# offical_board.net
KiCad netlist of a schematic drawn in EAGLE
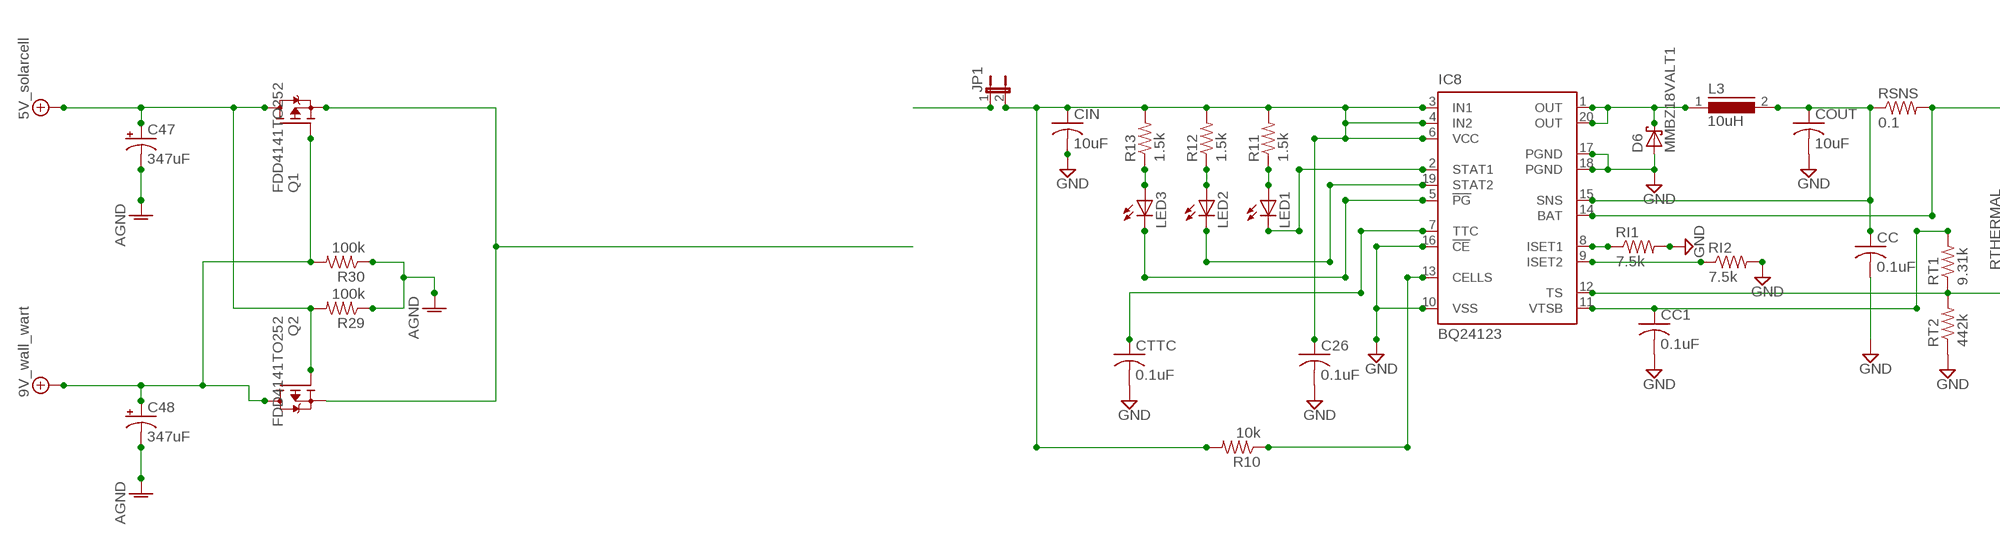
[diagram p0: schematic, sheet 1, part 1 of 2]
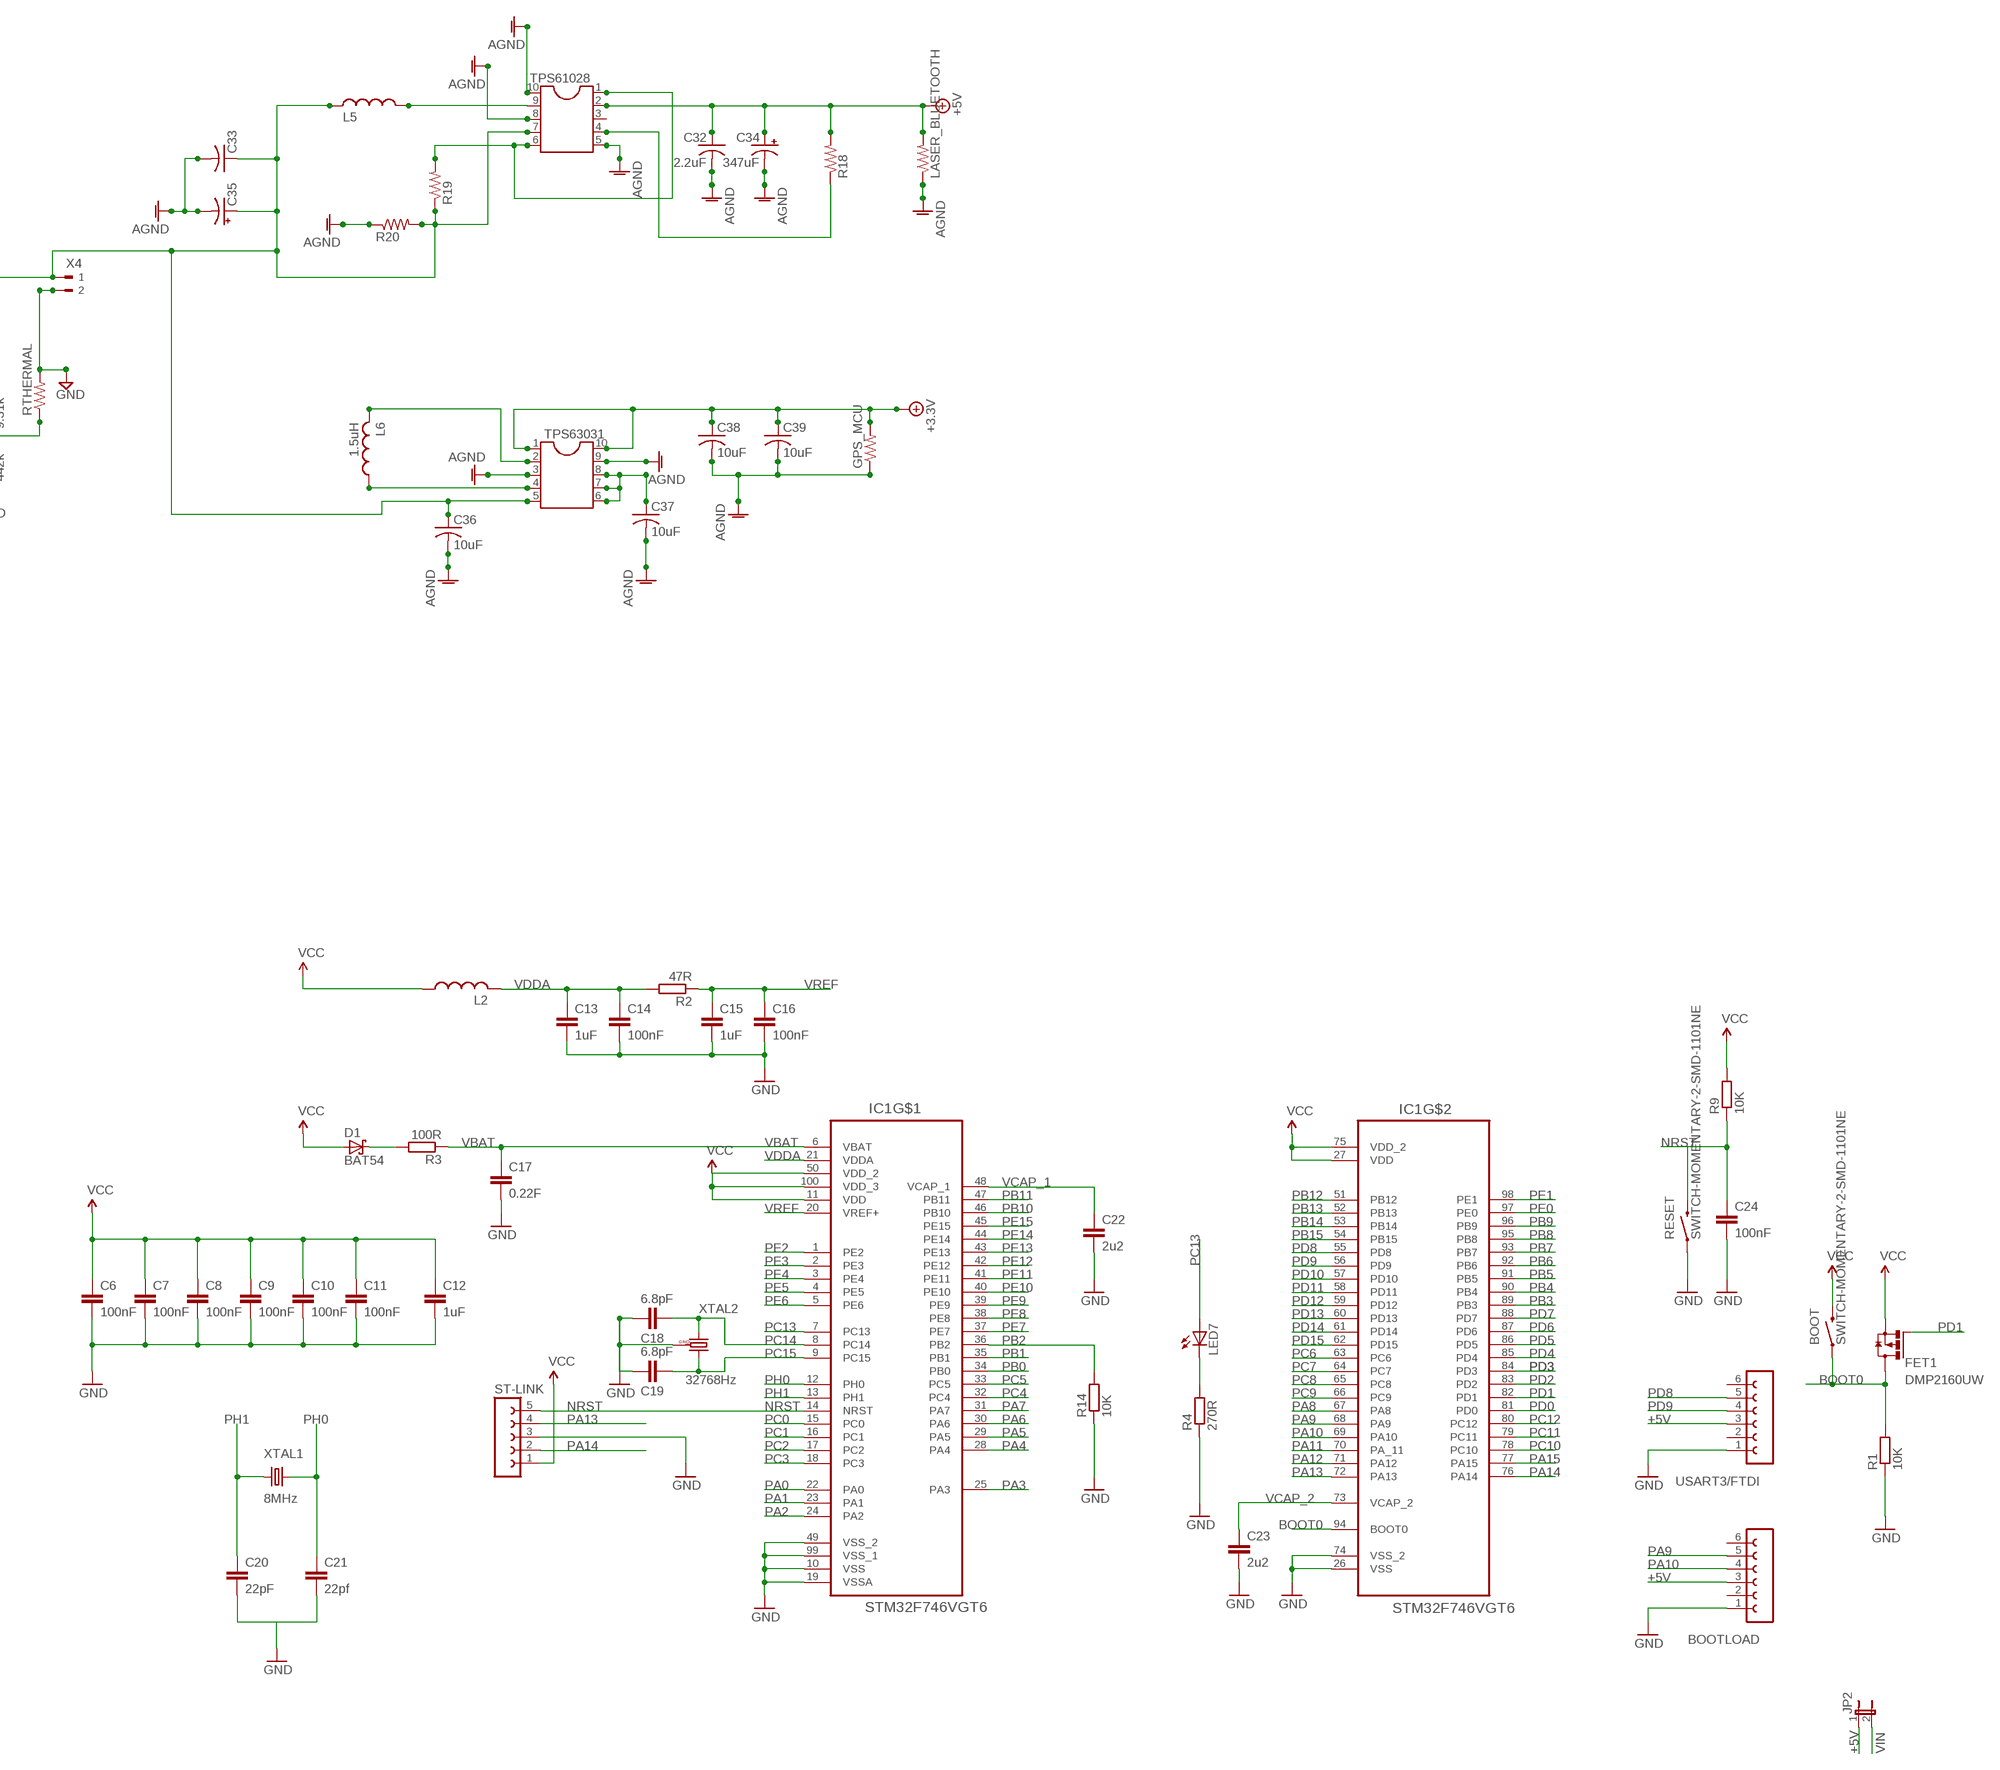
[diagram p1: schematic, sheet 1, part 2 of 2]

(export (version "E")
  (design (tool "Eeschema 10.0.6"))
  (components
    (comp (ref "BOOT")
      (value "SWITCH-MOMENTARY-2-SMD-1101NE")
      (footprint "eagle-import:TACTILE-SWITCH-1101NE")
      (libsource (lib "eagle-import") (part "SWITCH-MOMENTARY-2-SMD-1101NE"))
    )
    (comp (ref "BOOTLOAD")
      (value "FE06-1")
      (footprint "eagle-import:FE06")
      (libsource (lib "eagle-import") (part "FE06-1"))
    )
    (comp (ref "C6")
      (value "100nF")
      (footprint "eagle-import:C0603")
      (libsource (lib "eagle-import") (part "C-EUC0603"))
    )
    (comp (ref "C7")
      (value "100nF")
      (footprint "eagle-import:C0603")
      (libsource (lib "eagle-import") (part "C-EUC0603"))
    )
    (comp (ref "C8")
      (value "100nF")
      (footprint "eagle-import:C0603")
      (libsource (lib "eagle-import") (part "C-EUC0603"))
    )
    (comp (ref "C9")
      (value "100nF")
      (footprint "eagle-import:C0603")
      (libsource (lib "eagle-import") (part "C-EUC0603"))
    )
    (comp (ref "C10")
      (value "100nF")
      (footprint "eagle-import:C0603")
      (libsource (lib "eagle-import") (part "C-EUC0603"))
    )
    (comp (ref "C11")
      (value "100nF")
      (footprint "eagle-import:C0603")
      (libsource (lib "eagle-import") (part "C-EUC0603"))
    )
    (comp (ref "C12")
      (value "1uF")
      (footprint "eagle-import:C0603")
      (libsource (lib "eagle-import") (part "C-EUC0603"))
    )
    (comp (ref "C13")
      (value "1uF")
      (footprint "eagle-import:C0603")
      (libsource (lib "eagle-import") (part "C-EUC0603"))
    )
    (comp (ref "C14")
      (value "100nF")
      (footprint "eagle-import:C0603")
      (libsource (lib "eagle-import") (part "C-EUC0603"))
    )
    (comp (ref "C15")
      (value "1uF")
      (footprint "eagle-import:C0603")
      (libsource (lib "eagle-import") (part "C-EUC0603"))
    )
    (comp (ref "C16")
      (value "100nF")
      (footprint "eagle-import:C0603")
      (libsource (lib "eagle-import") (part "C-EUC0603"))
    )
    (comp (ref "C17")
      (value "0.22F")
      (footprint "eagle-import:C5B5")
      (libsource (lib "eagle-import") (part "C5/5"))
    )
    (comp (ref "C18")
      (value "6.8pF")
      (footprint "eagle-import:C0603")
      (libsource (lib "eagle-import") (part "C-EUC0603"))
    )
    (comp (ref "C19")
      (value "6.8pF")
      (footprint "eagle-import:C0603")
      (libsource (lib "eagle-import") (part "C-EUC0603"))
    )
    (comp (ref "C20")
      (value "22pF")
      (footprint "eagle-import:C0603")
      (libsource (lib "eagle-import") (part "C-EUC0603"))
    )
    (comp (ref "C21")
      (value "22pf")
      (footprint "eagle-import:C0603")
      (libsource (lib "eagle-import") (part "C-EUC0603"))
    )
    (comp (ref "C22")
      (value "2u2")
      (footprint "eagle-import:C0603")
      (libsource (lib "eagle-import") (part "C-EUC0603"))
    )
    (comp (ref "C23")
      (value "2u2")
      (footprint "eagle-import:C0603")
      (libsource (lib "eagle-import") (part "C-EUC0603"))
    )
    (comp (ref "C24")
      (value "100nF")
      (footprint "eagle-import:C0603")
      (libsource (lib "eagle-import") (part "C-EUC0603"))
    )
    (comp (ref "C26")
      (value "0.1uF")
      (footprint "eagle-import:C0805")
      (libsource (lib "eagle-import") (part "C-USC0805"))
    )
    (comp (ref "C32")
      (value "2.2uF")
      (footprint "eagle-import:C0603")
      (libsource (lib "eagle-import") (part "C-USC0603"))
    )
    (comp (ref "C33")
      (value "C-USC0603")
      (footprint "eagle-import:C0603")
      (libsource (lib "eagle-import") (part "C-USC0603"))
    )
    (comp (ref "C34")
      (value "347uF")
      (footprint "eagle-import:150CLZ-0810")
      (libsource (lib "eagle-import") (part "CPOL-US150CLZ-0810"))
    )
    (comp (ref "C35")
      (value "CPOL-US150CLZ-0810")
      (footprint "eagle-import:150CLZ-0810")
      (libsource (lib "eagle-import") (part "CPOL-US150CLZ-0810"))
    )
    (comp (ref "C36")
      (value "10uF")
      (footprint "eagle-import:C0603")
      (libsource (lib "eagle-import") (part "C-USC0603"))
    )
    (comp (ref "C37")
      (value "10uF")
      (footprint "eagle-import:C0603")
      (libsource (lib "eagle-import") (part "C-USC0603"))
    )
    (comp (ref "C38")
      (value "10uF")
      (footprint "eagle-import:C0603")
      (libsource (lib "eagle-import") (part "C-USC0603"))
    )
    (comp (ref "C39")
      (value "10uF")
      (footprint "eagle-import:C0603")
      (libsource (lib "eagle-import") (part "C-USC0603"))
    )
    (comp (ref "C47")
      (value "347uF")
      (footprint "eagle-import:150CLZ-0810")
      (libsource (lib "eagle-import") (part "CPOL-US150CLZ-0810"))
    )
    (comp (ref "C48")
      (value "347uF")
      (footprint "eagle-import:150CLZ-0810")
      (libsource (lib "eagle-import") (part "CPOL-US150CLZ-0810"))
    )
    (comp (ref "CC")
      (value "0.1uF")
      (footprint "eagle-import:C0805")
      (libsource (lib "eagle-import") (part "C-USC0805"))
    )
    (comp (ref "CC1")
      (value "0.1uF")
      (footprint "eagle-import:C0805")
      (libsource (lib "eagle-import") (part "C-USC0805"))
    )
    (comp (ref "CIN")
      (value "10uF")
      (footprint "eagle-import:C0805")
      (libsource (lib "eagle-import") (part "C-USC0805"))
    )
    (comp (ref "COUT")
      (value "10uF")
      (footprint "eagle-import:C0805")
      (libsource (lib "eagle-import") (part "C-USC0805"))
    )
    (comp (ref "CTTC")
      (value "0.1uF")
      (footprint "eagle-import:C0805")
      (libsource (lib "eagle-import") (part "C-USC0805"))
    )
    (comp (ref "D1")
      (value "BAT54")
      (footprint "eagle-import:SOT23")
      (libsource (lib "eagle-import") (part "BAT54"))
    )
    (comp (ref "D6")
      (value "MMBZ18VALT1")
      (footprint "eagle-import:C4111-15")
      (libsource (lib "eagle-import") (part "1N5908"))
    )
    (comp (ref "FET1")
      (value "DMP2160UW")
      (footprint "eagle-import:SUPER-SOT3")
      (libsource (lib "eagle-import") (part "FDN360P"))
    )
    (comp (ref "GPS_MCU")
      (value "R-US_R0603")
      (footprint "eagle-import:R0603")
      (libsource (lib "eagle-import") (part "R-US_R0603"))
    )
    (comp (ref "IC1")
      (value "STM32F746VGT6")
      (footprint "eagle-import:QFP50P1600X1600X160-100N")
      (libsource (lib "eagle-import") (part "STM32F746VGT6"))
    )
    (comp (ref "IC8")
      (value "BQ24123")
      (footprint "eagle-import:QFN20_3,5X4,5")
      (fields (field (name "MPN") "BQ24123RHLT"))
      (libsource (lib "eagle-import") (part "BQ24123"))
    )
    (comp (ref "JP1")
      (value "JP1E")
      (footprint "eagle-import:JP1")
      (libsource (lib "eagle-import") (part "JP1E"))
    )
    (comp (ref "JP2")
      (value "JP1E")
      (footprint "eagle-import:JP1")
      (libsource (lib "eagle-import") (part "JP1E"))
    )
    (comp (ref "L2")
      (value "RCL_L-USL0603")
      (footprint "eagle-import:RCL_L0603")
      (libsource (lib "eagle-import") (part "RCL_L-USL0603"))
    )
    (comp (ref "L3")
      (value "10uH")
      (footprint "eagle-import:DR73")
      (libsource (lib "eagle-import") (part "DR73"))
    )
    (comp (ref "L5")
      (value "L-USL2825P")
      (footprint "eagle-import:L2825P")
      (libsource (lib "eagle-import") (part "L-USL2825P"))
    )
    (comp (ref "L6")
      (value "1.5uH")
      (footprint "eagle-import:L2825P")
      (libsource (lib "eagle-import") (part "L-USL2825P"))
    )
    (comp (ref "LASER_BLUETOOTH")
      (value "R-US_R0603")
      (footprint "eagle-import:R0603")
      (libsource (lib "eagle-import") (part "R-US_R0603"))
    )
    (comp (ref "LED1")
      (value "SFH482")
      (footprint "eagle-import:SFH482")
      (libsource (lib "eagle-import") (part "SFH482"))
    )
    (comp (ref "LED2")
      (value "SFH482")
      (footprint "eagle-import:SFH482")
      (libsource (lib "eagle-import") (part "SFH482"))
    )
    (comp (ref "LED3")
      (value "SFH482")
      (footprint "eagle-import:SFH482")
      (libsource (lib "eagle-import") (part "SFH482"))
    )
    (comp (ref "LED7")
      (value "LEDCHIP-LED0603")
      (footprint "eagle-import:CHIP-LED0603")
      (libsource (lib "eagle-import") (part "LEDCHIP-LED0603"))
    )
    (comp (ref "Q1")
      (value "FDD4141TO252")
      (footprint "eagle-import:TO252")
      (libsource (lib "eagle-import") (part "FDD4141TO252"))
    )
    (comp (ref "Q2")
      (value "FDD4141TO252")
      (footprint "eagle-import:TO252")
      (libsource (lib "eagle-import") (part "FDD4141TO252"))
    )
    (comp (ref "R1")
      (value "10K")
      (footprint "eagle-import:R0603")
      (libsource (lib "eagle-import") (part "R-EU_R0603"))
    )
    (comp (ref "R2")
      (value "47R")
      (footprint "eagle-import:R0603")
      (libsource (lib "eagle-import") (part "R-EU_R0603"))
    )
    (comp (ref "R3")
      (value "100R")
      (footprint "eagle-import:R0603")
      (libsource (lib "eagle-import") (part "resistor_R-EU_R0603"))
    )
    (comp (ref "R4")
      (value "270R")
      (footprint "eagle-import:R0603")
      (libsource (lib "eagle-import") (part "resistor_R-EU_R0603"))
    )
    (comp (ref "R9")
      (value "10K")
      (footprint "eagle-import:R0603")
      (libsource (lib "eagle-import") (part "R-EU_R0603"))
    )
    (comp (ref "R10")
      (value "10k")
      (footprint "eagle-import:R0805")
      (libsource (lib "eagle-import") (part "R-US_R0805"))
    )
    (comp (ref "R11")
      (value "1.5k")
      (footprint "eagle-import:R0805")
      (libsource (lib "eagle-import") (part "R-US_R0805"))
    )
    (comp (ref "R12")
      (value "1.5k")
      (footprint "eagle-import:R0805")
      (libsource (lib "eagle-import") (part "R-US_R0805"))
    )
    (comp (ref "R13")
      (value "1.5k")
      (footprint "eagle-import:R0805")
      (libsource (lib "eagle-import") (part "R-US_R0805"))
    )
    (comp (ref "R14")
      (value "10K")
      (footprint "eagle-import:R0603")
      (libsource (lib "eagle-import") (part "R-EU_R0603"))
    )
    (comp (ref "R18")
      (value "R-US_R0603")
      (footprint "eagle-import:R0603")
      (libsource (lib "eagle-import") (part "R-US_R0603"))
    )
    (comp (ref "R19")
      (value "R-US_R0603")
      (footprint "eagle-import:R0603")
      (libsource (lib "eagle-import") (part "R-US_R0603"))
    )
    (comp (ref "R20")
      (value "R-US_R0603")
      (footprint "eagle-import:R0603")
      (libsource (lib "eagle-import") (part "R-US_R0603"))
    )
    (comp (ref "R29")
      (value "100k")
      (footprint "eagle-import:R0603")
      (libsource (lib "eagle-import") (part "R-US_R0603"))
    )
    (comp (ref "R30")
      (value "100k")
      (footprint "eagle-import:R0603")
      (libsource (lib "eagle-import") (part "R-US_R0603"))
    )
    (comp (ref "RESET")
      (value "SWITCH-MOMENTARY-2-SMD-1101NE")
      (footprint "eagle-import:TACTILE-SWITCH-1101NE")
      (libsource (lib "eagle-import") (part "SWITCH-MOMENTARY-2-SMD-1101NE"))
    )
    (comp (ref "RI1")
      (value "7.5k")
      (footprint "eagle-import:R0805")
      (libsource (lib "eagle-import") (part "R-US_R0805"))
    )
    (comp (ref "RI2")
      (value "7.5k")
      (footprint "eagle-import:R0805")
      (libsource (lib "eagle-import") (part "R-US_R0805"))
    )
    (comp (ref "RSNS")
      (value "0.1")
      (footprint "eagle-import:R1206")
      (libsource (lib "eagle-import") (part "R-US_R1206"))
    )
    (comp (ref "RT1")
      (value "9.31k")
      (footprint "eagle-import:R0805")
      (libsource (lib "eagle-import") (part "R-US_R0805"))
    )
    (comp (ref "RT2")
      (value "442k")
      (footprint "eagle-import:R0805")
      (libsource (lib "eagle-import") (part "R-US_R0805"))
    )
    (comp (ref "RTHERMAL")
      (value "R-US_R0805")
      (footprint "eagle-import:R0805")
      (libsource (lib "eagle-import") (part "R-US_R0805"))
    )
    (comp (ref "ST-LINK")
      (value "FE05-1")
      (footprint "eagle-import:FE05-1")
      (libsource (lib "eagle-import") (part "FE05-1"))
    )
    (comp (ref "TPS61028")
      (value "DIL10")
      (footprint "eagle-import:DIL10")
      (libsource (lib "eagle-import") (part "DIL10"))
    )
    (comp (ref "TPS63031")
      (value "DIL10")
      (footprint "eagle-import:DIL10")
      (libsource (lib "eagle-import") (part "DIL10"))
    )
    (comp (ref "USART3/FTDI")
      (value "FE06-1")
      (footprint "eagle-import:FE06")
      (libsource (lib "eagle-import") (part "FE06-1"))
    )
    (comp (ref "X4")
      (value "90-2")
      (footprint "eagle-import:90-2")
      (libsource (lib "eagle-import") (part "90-2"))
    )
    (comp (ref "XTAL1")
      (value "8MHz")
      (footprint "eagle-import:HC49U-V")
      (libsource (lib "eagle-import") (part "CRYSTALHC49U-V"))
    )
    (comp (ref "XTAL2")
      (value "32768Hz")
      (footprint "eagle-import:CRYSTAL_TC26H_3_REPAIR_SMD_SMALL_PITCH")
      (libsource (lib "eagle-import") (part "CRYSTAL_Q_GNDS"))
    )
  )
  (nets
    (net (code "1") (name "+3.3V") (class "Default")
      (node (ref "BOOTLOAD") (pin "3") (pinfunction "3_3") (pintype "passive"))
      (node (ref "C32") (pin "1") (pinfunction "1_1") (pintype "passive"))
      (node (ref "C34") (pin "+") (pinfunction "+_+") (pintype "passive"))
      (node (ref "C38") (pin "1") (pinfunction "1_1") (pintype "passive"))
      (node (ref "C39") (pin "1") (pinfunction "1_1") (pintype "passive"))
      (node (ref "C47") (pin "+") (pinfunction "+_+") (pintype "passive"))
      (node (ref "C48") (pin "+") (pinfunction "+_+") (pintype "passive"))
      (node (ref "GPS_MCU") (pin "2") (pinfunction "2_2") (pintype "passive"))
      (node (ref "JP2") (pin "1") (pinfunction "1_1") (pintype "passive"))
      (node (ref "LASER_BLUETOOTH") (pin "2") (pinfunction "2_2") (pintype "passive"))
      (node (ref "Q1") (pin "1") (pinfunction "G_1") (pintype "passive"))
      (node (ref "Q1") (pin "3") (pinfunction "D_3") (pintype "passive"))
      (node (ref "Q2") (pin "1") (pinfunction "G_1") (pintype "passive"))
      (node (ref "Q2") (pin "3") (pinfunction "D_3") (pintype "passive"))
      (node (ref "R18") (pin "2") (pinfunction "2_2") (pintype "passive"))
      (node (ref "R29") (pin "2") (pinfunction "2_2") (pintype "passive"))
      (node (ref "R30") (pin "2") (pinfunction "2_2") (pintype "passive"))
      (node (ref "TPS61028") (pin "2") (pinfunction "2_2") (pintype "passive"))
      (node (ref "TPS63031") (pin "1") (pinfunction "1_1") (pintype "passive"))
      (node (ref "TPS63031") (pin "10") (pinfunction "10_10") (pintype "passive"))
      (node (ref "USART3/FTDI") (pin "3") (pinfunction "3_3") (pintype "passive"))
    )
    (net (code "2") (name "/BOOT0") (class "Default")
      (node (ref "BOOT") (pin "P$1") (pinfunction "1_P$1") (pintype "passive"))
      (node (ref "FET1") (pin "3") (pinfunction "D_3") (pintype "passive"))
      (node (ref "IC1") (pin "94") (pinfunction "BOOT0_94") (pintype "input"))
      (node (ref "R1") (pin "2") (pinfunction "2_2") (pintype "passive"))
    )
    (net (code "3") (name "/NRST") (class "Default")
      (node (ref "C24") (pin "1") (pinfunction "1_1") (pintype "passive"))
      (node (ref "IC1") (pin "14") (pinfunction "NRST_14") (pintype "bidirectional"))
      (node (ref "R9") (pin "1") (pinfunction "1_1") (pintype "passive"))
      (node (ref "RESET") (pin "P$2") (pinfunction "2_P$2") (pintype "passive"))
      (node (ref "ST-LINK") (pin "5") (pinfunction "5_5") (pintype "passive"))
    )
    (net (code "4") (name "/PA0") (class "Default")
      (node (ref "IC1") (pin "22") (pinfunction "PA0_22") (pintype "bidirectional"))
    )
    (net (code "5") (name "/PA1") (class "Default")
      (node (ref "IC1") (pin "23") (pinfunction "PA1_23") (pintype "bidirectional"))
    )
    (net (code "6") (name "/PA2") (class "Default")
      (node (ref "IC1") (pin "24") (pinfunction "PA2_24") (pintype "bidirectional"))
    )
    (net (code "7") (name "/PA3") (class "Default")
      (node (ref "IC1") (pin "25") (pinfunction "PA3_25") (pintype "bidirectional"))
    )
    (net (code "8") (name "/PA4") (class "Default")
      (node (ref "IC1") (pin "28") (pinfunction "PA4_28") (pintype "bidirectional"))
    )
    (net (code "9") (name "/PA5") (class "Default")
      (node (ref "IC1") (pin "29") (pinfunction "PA5_29") (pintype "bidirectional"))
    )
    (net (code "10") (name "/PA6") (class "Default")
      (node (ref "IC1") (pin "30") (pinfunction "PA6_30") (pintype "bidirectional"))
    )
    (net (code "11") (name "/PA7") (class "Default")
      (node (ref "IC1") (pin "31") (pinfunction "PA7_31") (pintype "bidirectional"))
    )
    (net (code "12") (name "/PA8") (class "Default")
      (node (ref "IC1") (pin "67") (pinfunction "PA8_67") (pintype "bidirectional"))
    )
    (net (code "13") (name "/PA9") (class "Default")
      (node (ref "BOOTLOAD") (pin "5") (pinfunction "5_5") (pintype "passive"))
      (node (ref "IC1") (pin "68") (pinfunction "PA9_68") (pintype "bidirectional"))
    )
    (net (code "14") (name "/PA10") (class "Default")
      (node (ref "BOOTLOAD") (pin "4") (pinfunction "4_4") (pintype "passive"))
      (node (ref "IC1") (pin "69") (pinfunction "PA10_69") (pintype "bidirectional"))
    )
    (net (code "15") (name "/PA11") (class "Default")
      (node (ref "IC1") (pin "70") (pinfunction "PA_11_70") (pintype "bidirectional"))
    )
    (net (code "16") (name "/PA12") (class "Default")
      (node (ref "IC1") (pin "71") (pinfunction "PA12_71") (pintype "bidirectional"))
    )
    (net (code "17") (name "/PA13") (class "Default")
      (node (ref "IC1") (pin "72") (pinfunction "PA13_72") (pintype "bidirectional"))
      (node (ref "ST-LINK") (pin "4") (pinfunction "4_4") (pintype "passive"))
    )
    (net (code "18") (name "/PA14") (class "Default")
      (node (ref "IC1") (pin "76") (pinfunction "PA14_76") (pintype "bidirectional"))
      (node (ref "ST-LINK") (pin "2") (pinfunction "2_2") (pintype "passive"))
    )
    (net (code "19") (name "/PA15") (class "Default")
      (node (ref "IC1") (pin "77") (pinfunction "PA15_77") (pintype "bidirectional"))
    )
    (net (code "20") (name "/PB0") (class "Default")
      (node (ref "IC1") (pin "34") (pinfunction "PB0_34") (pintype "bidirectional"))
    )
    (net (code "21") (name "/PB1") (class "Default")
      (node (ref "IC1") (pin "35") (pinfunction "PB1_35") (pintype "bidirectional"))
    )
    (net (code "22") (name "/PB2") (class "Default")
      (node (ref "IC1") (pin "36") (pinfunction "PB2_36") (pintype "bidirectional"))
      (node (ref "R14") (pin "2") (pinfunction "2_2") (pintype "passive"))
    )
    (net (code "23") (name "/PB3") (class "Default")
      (node (ref "IC1") (pin "89") (pinfunction "PB3_89") (pintype "bidirectional"))
    )
    (net (code "24") (name "/PB4") (class "Default")
      (node (ref "IC1") (pin "90") (pinfunction "PB4_90") (pintype "bidirectional"))
    )
    (net (code "25") (name "/PB5") (class "Default")
      (node (ref "IC1") (pin "91") (pinfunction "PB5_91") (pintype "bidirectional"))
    )
    (net (code "26") (name "/PB6") (class "Default")
      (node (ref "IC1") (pin "92") (pinfunction "PB6_92") (pintype "bidirectional"))
    )
    (net (code "27") (name "/PB7") (class "Default")
      (node (ref "IC1") (pin "93") (pinfunction "PB7_93") (pintype "bidirectional"))
    )
    (net (code "28") (name "/PB8") (class "Default")
      (node (ref "IC1") (pin "95") (pinfunction "PB8_95") (pintype "bidirectional"))
    )
    (net (code "29") (name "/PB9") (class "Default")
      (node (ref "IC1") (pin "96") (pinfunction "PB9_96") (pintype "bidirectional"))
    )
    (net (code "30") (name "/PB10") (class "Default")
      (node (ref "IC1") (pin "46") (pinfunction "PB10_46") (pintype "bidirectional"))
    )
    (net (code "31") (name "/PB11") (class "Default")
      (node (ref "IC1") (pin "47") (pinfunction "PB11_47") (pintype "bidirectional"))
    )
    (net (code "32") (name "/PB12") (class "Default")
      (node (ref "IC1") (pin "51") (pinfunction "PB12_51") (pintype "bidirectional"))
    )
    (net (code "33") (name "/PB13") (class "Default")
      (node (ref "IC1") (pin "52") (pinfunction "PB13_52") (pintype "bidirectional"))
    )
    (net (code "34") (name "/PB14") (class "Default")
      (node (ref "IC1") (pin "53") (pinfunction "PB14_53") (pintype "bidirectional"))
    )
    (net (code "35") (name "/PB15") (class "Default")
      (node (ref "IC1") (pin "54") (pinfunction "PB15_54") (pintype "bidirectional"))
    )
    (net (code "36") (name "/PC0") (class "Default")
      (node (ref "IC1") (pin "15") (pinfunction "PC0_15") (pintype "bidirectional"))
    )
    (net (code "37") (name "/PC1") (class "Default")
      (node (ref "IC1") (pin "16") (pinfunction "PC1_16") (pintype "bidirectional"))
    )
    (net (code "38") (name "/PC2") (class "Default")
      (node (ref "IC1") (pin "17") (pinfunction "PC2_17") (pintype "bidirectional"))
    )
    (net (code "39") (name "/PC3") (class "Default")
      (node (ref "IC1") (pin "18") (pinfunction "PC3_18") (pintype "bidirectional"))
    )
    (net (code "40") (name "/PC4") (class "Default")
      (node (ref "IC1") (pin "32") (pinfunction "PC4_32") (pintype "bidirectional"))
    )
    (net (code "41") (name "/PC5") (class "Default")
      (node (ref "IC1") (pin "33") (pinfunction "PC5_33") (pintype "bidirectional"))
    )
    (net (code "42") (name "/PC6") (class "Default")
      (node (ref "IC1") (pin "63") (pinfunction "PC6_63") (pintype "bidirectional"))
    )
    (net (code "43") (name "/PC7") (class "Default")
      (node (ref "IC1") (pin "64") (pinfunction "PC7_64") (pintype "bidirectional"))
    )
    (net (code "44") (name "/PC8") (class "Default")
      (node (ref "IC1") (pin "65") (pinfunction "PC8_65") (pintype "bidirectional"))
    )
    (net (code "45") (name "/PC9") (class "Default")
      (node (ref "IC1") (pin "66") (pinfunction "PC9_66") (pintype "bidirectional"))
    )
    (net (code "46") (name "/PC10") (class "Default")
      (node (ref "IC1") (pin "78") (pinfunction "PC10_78") (pintype "bidirectional"))
    )
    (net (code "47") (name "/PC11") (class "Default")
      (node (ref "IC1") (pin "79") (pinfunction "PC11_79") (pintype "bidirectional"))
    )
    (net (code "48") (name "/PC12") (class "Default")
      (node (ref "IC1") (pin "80") (pinfunction "PC12_80") (pintype "bidirectional"))
    )
    (net (code "49") (name "/PC13") (class "Default")
      (node (ref "IC1") (pin "7") (pinfunction "PC13_7") (pintype "bidirectional"))
      (node (ref "LED7") (pin "A") (pinfunction "A_A") (pintype "passive"))
    )
    (net (code "50") (name "/PC14") (class "Default")
      (node (ref "C18") (pin "1") (pinfunction "1_1") (pintype "passive"))
      (node (ref "IC1") (pin "8") (pinfunction "PC14_8") (pintype "bidirectional"))
      (node (ref "XTAL2") (pin "1") (pinfunction "1_1") (pintype "passive"))
    )
    (net (code "51") (name "/PC15") (class "Default")
      (node (ref "C19") (pin "1") (pinfunction "1_1") (pintype "passive"))
      (node (ref "IC1") (pin "9") (pinfunction "PC15_9") (pintype "bidirectional"))
      (node (ref "XTAL2") (pin "2") (pinfunction "2_2") (pintype "passive"))
    )
    (net (code "52") (name "/PD0") (class "Default")
      (node (ref "IC1") (pin "81") (pinfunction "PD0_81") (pintype "bidirectional"))
    )
    (net (code "53") (name "/PD1") (class "Default")
      (node (ref "FET1") (pin "1") (pinfunction "G_1") (pintype "passive"))
      (node (ref "IC1") (pin "82") (pinfunction "PD1_82") (pintype "bidirectional"))
    )
    (net (code "54") (name "/PD2") (class "Default")
      (node (ref "IC1") (pin "83") (pinfunction "PD2_83") (pintype "bidirectional"))
    )
    (net (code "55") (name "/PD3") (class "Default")
      (node (ref "IC1") (pin "84") (pinfunction "PD3_84") (pintype "bidirectional"))
    )
    (net (code "56") (name "/PD4") (class "Default")
      (node (ref "IC1") (pin "85") (pinfunction "PD4_85") (pintype "bidirectional"))
    )
    (net (code "57") (name "/PD5") (class "Default")
      (node (ref "IC1") (pin "86") (pinfunction "PD5_86") (pintype "bidirectional"))
    )
    (net (code "58") (name "/PD6") (class "Default")
      (node (ref "IC1") (pin "87") (pinfunction "PD6_87") (pintype "bidirectional"))
    )
    (net (code "59") (name "/PD7") (class "Default")
      (node (ref "IC1") (pin "88") (pinfunction "PD7_88") (pintype "bidirectional"))
    )
    (net (code "60") (name "/PD8") (class "Default")
      (node (ref "IC1") (pin "55") (pinfunction "PD8_55") (pintype "bidirectional"))
      (node (ref "USART3/FTDI") (pin "5") (pinfunction "5_5") (pintype "passive"))
    )
    (net (code "61") (name "/PD9") (class "Default")
      (node (ref "IC1") (pin "56") (pinfunction "PD9_56") (pintype "bidirectional"))
      (node (ref "USART3/FTDI") (pin "4") (pinfunction "4_4") (pintype "passive"))
    )
    (net (code "62") (name "/PD10") (class "Default")
      (node (ref "IC1") (pin "57") (pinfunction "PD10_57") (pintype "bidirectional"))
    )
    (net (code "63") (name "/PD11") (class "Default")
      (node (ref "IC1") (pin "58") (pinfunction "PD11_58") (pintype "bidirectional"))
    )
    (net (code "64") (name "/PD12") (class "Default")
      (node (ref "IC1") (pin "59") (pinfunction "PD12_59") (pintype "bidirectional"))
    )
    (net (code "65") (name "/PD13") (class "Default")
      (node (ref "IC1") (pin "60") (pinfunction "PD13_60") (pintype "bidirectional"))
    )
    (net (code "66") (name "/PD14") (class "Default")
      (node (ref "IC1") (pin "61") (pinfunction "PD14_61") (pintype "bidirectional"))
    )
    (net (code "67") (name "/PD15") (class "Default")
      (node (ref "IC1") (pin "62") (pinfunction "PD15_62") (pintype "bidirectional"))
    )
    (net (code "68") (name "/PE0") (class "Default")
      (node (ref "IC1") (pin "97") (pinfunction "PE0_97") (pintype "bidirectional"))
    )
    (net (code "69") (name "/PE1") (class "Default")
      (node (ref "IC1") (pin "98") (pinfunction "PE1_98") (pintype "bidirectional"))
    )
    (net (code "70") (name "/PE2") (class "Default")
      (node (ref "IC1") (pin "1") (pinfunction "PE2_1") (pintype "bidirectional"))
    )
    (net (code "71") (name "/PE3") (class "Default")
      (node (ref "IC1") (pin "2") (pinfunction "PE3_2") (pintype "bidirectional"))
    )
    (net (code "72") (name "/PE4") (class "Default")
      (node (ref "IC1") (pin "3") (pinfunction "PE4_3") (pintype "bidirectional"))
    )
    (net (code "73") (name "/PE5") (class "Default")
      (node (ref "IC1") (pin "4") (pinfunction "PE5_4") (pintype "bidirectional"))
    )
    (net (code "74") (name "/PE6") (class "Default")
      (node (ref "IC1") (pin "5") (pinfunction "PE6_5") (pintype "bidirectional"))
    )
    (net (code "75") (name "/PE7") (class "Default")
      (node (ref "IC1") (pin "37") (pinfunction "PE7_37") (pintype "bidirectional"))
    )
    (net (code "76") (name "/PE8") (class "Default")
      (node (ref "IC1") (pin "38") (pinfunction "PE8_38") (pintype "bidirectional"))
    )
    (net (code "77") (name "/PE9") (class "Default")
      (node (ref "IC1") (pin "39") (pinfunction "PE9_39") (pintype "bidirectional"))
    )
    (net (code "78") (name "/PE10") (class "Default")
      (node (ref "IC1") (pin "40") (pinfunction "PE10_40") (pintype "bidirectional"))
    )
    (net (code "79") (name "/PE11") (class "Default")
      (node (ref "IC1") (pin "41") (pinfunction "PE11_41") (pintype "bidirectional"))
    )
    (net (code "80") (name "/PE12") (class "Default")
      (node (ref "IC1") (pin "42") (pinfunction "PE12_42") (pintype "bidirectional"))
    )
    (net (code "81") (name "/PE13") (class "Default")
      (node (ref "IC1") (pin "43") (pinfunction "PE13_43") (pintype "bidirectional"))
    )
    (net (code "82") (name "/PE14") (class "Default")
      (node (ref "IC1") (pin "44") (pinfunction "PE14_44") (pintype "bidirectional"))
    )
    (net (code "83") (name "/PE15") (class "Default")
      (node (ref "IC1") (pin "45") (pinfunction "PE15_45") (pintype "bidirectional"))
    )
    (net (code "84") (name "/PH0") (class "Default")
      (node (ref "C21") (pin "1") (pinfunction "1_1") (pintype "passive"))
      (node (ref "IC1") (pin "12") (pinfunction "PH0_12") (pintype "bidirectional"))
      (node (ref "XTAL1") (pin "2") (pinfunction "2_2") (pintype "passive"))
    )
    (net (code "85") (name "/PH1") (class "Default")
      (node (ref "C20") (pin "1") (pinfunction "1_1") (pintype "passive"))
      (node (ref "IC1") (pin "13") (pinfunction "PH1_13") (pintype "bidirectional"))
      (node (ref "XTAL1") (pin "1") (pinfunction "1_1") (pintype "passive"))
    )
    (net (code "86") (name "/VBAT") (class "Default")
      (node (ref "C17") (pin "1") (pinfunction "1_1") (pintype "passive"))
      (node (ref "IC1") (pin "6") (pinfunction "VBAT_6") (pintype "power_in"))
      (node (ref "R3") (pin "1") (pinfunction "1_1") (pintype "passive"))
    )
    (net (code "87") (name "/VCAP_1") (class "Default")
      (node (ref "C22") (pin "1") (pinfunction "1_1") (pintype "passive"))
      (node (ref "IC1") (pin "48") (pinfunction "VCAP_1_48") (pintype "power_in"))
    )
    (net (code "88") (name "/VCAP_2") (class "Default")
      (node (ref "C23") (pin "1") (pinfunction "1_1") (pintype "passive"))
      (node (ref "IC1") (pin "73") (pinfunction "VCAP_2_73") (pintype "power_in"))
    )
    (net (code "89") (name "/VDDA") (class "Default")
      (node (ref "C13") (pin "1") (pinfunction "1_1") (pintype "passive"))
      (node (ref "C14") (pin "1") (pinfunction "1_1") (pintype "passive"))
      (node (ref "IC1") (pin "21") (pinfunction "VDDA_21") (pintype "power_in"))
      (node (ref "L2") (pin "2") (pinfunction "2_2") (pintype "passive"))
      (node (ref "R2") (pin "2") (pinfunction "2_2") (pintype "passive"))
    )
    (net (code "90") (name "/VIN") (class "Default")
      (node (ref "JP2") (pin "2") (pinfunction "2_2") (pintype "passive"))
    )
    (net (code "91") (name "/VREF") (class "Default")
      (node (ref "C15") (pin "1") (pinfunction "1_1") (pintype "passive"))
      (node (ref "C16") (pin "1") (pinfunction "1_1") (pintype "passive"))
      (node (ref "IC1") (pin "20") (pinfunction "VREF+_20") (pintype "power_in"))
      (node (ref "R2") (pin "1") (pinfunction "1_1") (pintype "passive"))
    )
    (net (code "92") (name "AGND") (class "Default")
      (node (ref "C32") (pin "2") (pinfunction "2_2") (pintype "passive"))
      (node (ref "C33") (pin "2") (pinfunction "2_2") (pintype "passive"))
      (node (ref "C34") (pin "-") (pinfunction "-_-") (pintype "passive"))
      (node (ref "C35") (pin "-") (pinfunction "-_-") (pintype "passive"))
      (node (ref "C36") (pin "2") (pinfunction "2_2") (pintype "passive"))
      (node (ref "C37") (pin "2") (pinfunction "2_2") (pintype "passive"))
      (node (ref "C38") (pin "2") (pinfunction "2_2") (pintype "passive"))
      (node (ref "C39") (pin "2") (pinfunction "2_2") (pintype "passive"))
      (node (ref "C47") (pin "-") (pinfunction "-_-") (pintype "passive"))
      (node (ref "C48") (pin "-") (pinfunction "-_-") (pintype "passive"))
      (node (ref "GPS_MCU") (pin "1") (pinfunction "1_1") (pintype "passive"))
      (node (ref "LASER_BLUETOOTH") (pin "1") (pinfunction "1_1") (pintype "passive"))
      (node (ref "R20") (pin "1") (pinfunction "1_1") (pintype "passive"))
      (node (ref "R29") (pin "1") (pinfunction "1_1") (pintype "passive"))
      (node (ref "R30") (pin "1") (pinfunction "1_1") (pintype "passive"))
      (node (ref "TPS61028") (pin "10") (pinfunction "10_10") (pintype "passive"))
      (node (ref "TPS61028") (pin "5") (pinfunction "5_5") (pintype "passive"))
      (node (ref "TPS61028") (pin "8") (pinfunction "8_8") (pintype "passive"))
      (node (ref "TPS63031") (pin "3") (pinfunction "3_3") (pintype "passive"))
      (node (ref "TPS63031") (pin "9") (pinfunction "9_9") (pintype "passive"))
    )
    (net (code "93") (name "GND") (class "Default")
      (node (ref "BOOTLOAD") (pin "1") (pinfunction "1_1") (pintype "passive"))
      (node (ref "C10") (pin "2") (pinfunction "2_2") (pintype "passive"))
      (node (ref "C11") (pin "2") (pinfunction "2_2") (pintype "passive"))
      (node (ref "C12") (pin "2") (pinfunction "2_2") (pintype "passive"))
      (node (ref "C13") (pin "2") (pinfunction "2_2") (pintype "passive"))
      (node (ref "C14") (pin "2") (pinfunction "2_2") (pintype "passive"))
      (node (ref "C15") (pin "2") (pinfunction "2_2") (pintype "passive"))
      (node (ref "C16") (pin "2") (pinfunction "2_2") (pintype "passive"))
      (node (ref "C17") (pin "2") (pinfunction "2_2") (pintype "passive"))
      (node (ref "C18") (pin "2") (pinfunction "2_2") (pintype "passive"))
      (node (ref "C19") (pin "2") (pinfunction "2_2") (pintype "passive"))
      (node (ref "C20") (pin "2") (pinfunction "2_2") (pintype "passive"))
      (node (ref "C21") (pin "2") (pinfunction "2_2") (pintype "passive"))
      (node (ref "C22") (pin "2") (pinfunction "2_2") (pintype "passive"))
      (node (ref "C23") (pin "2") (pinfunction "2_2") (pintype "passive"))
      (node (ref "C24") (pin "2") (pinfunction "2_2") (pintype "passive"))
      (node (ref "C26") (pin "2") (pinfunction "2_2") (pintype "passive"))
      (node (ref "C6") (pin "2") (pinfunction "2_2") (pintype "passive"))
      (node (ref "C7") (pin "2") (pinfunction "2_2") (pintype "passive"))
      (node (ref "C8") (pin "2") (pinfunction "2_2") (pintype "passive"))
      (node (ref "C9") (pin "2") (pinfunction "2_2") (pintype "passive"))
      (node (ref "CC") (pin "2") (pinfunction "2_2") (pintype "passive"))
      (node (ref "CC1") (pin "2") (pinfunction "2_2") (pintype "passive"))
      (node (ref "CIN") (pin "2") (pinfunction "2_2") (pintype "passive"))
      (node (ref "COUT") (pin "2") (pinfunction "2_2") (pintype "passive"))
      (node (ref "CTTC") (pin "2") (pinfunction "2_2") (pintype "passive"))
      (node (ref "D6") (pin "A") (pinfunction "A_A") (pintype "passive"))
      (node (ref "IC1") (pin "10") (pinfunction "VSS_10") (pintype "passive"))
      (node (ref "IC1") (pin "19") (pinfunction "VSSA_19") (pintype "passive"))
      (node (ref "IC1") (pin "26") (pinfunction "VSS_26") (pintype "passive"))
      (node (ref "IC1") (pin "49") (pinfunction "VSS_2_49") (pintype "passive"))
      (node (ref "IC1") (pin "74") (pinfunction "VSS_2_74") (pintype "passive"))
      (node (ref "IC1") (pin "99") (pinfunction "VSS_1_99") (pintype "power_in"))
      (node (ref "IC8") (pin "10") (pinfunction "VSS_10") (pintype "power_in"))
      (node (ref "IC8") (pin "16") (pinfunction "~{CE}_16") (pintype "input"))
      (node (ref "IC8") (pin "17") (pinfunction "PGND_17") (pintype "input"))
      (node (ref "IC8") (pin "18") (pinfunction "PGND_18") (pintype "input"))
      (node (ref "R1") (pin "1") (pinfunction "1_1") (pintype "passive"))
      (node (ref "R14") (pin "1") (pinfunction "1_1") (pintype "passive"))
      (node (ref "R4") (pin "1") (pinfunction "1_1") (pintype "passive"))
      (node (ref "RESET") (pin "P$1") (pinfunction "1_P$1") (pintype "passive"))
      (node (ref "RI1") (pin "2") (pinfunction "2_2") (pintype "passive"))
      (node (ref "RI2") (pin "2") (pinfunction "2_2") (pintype "passive"))
      (node (ref "RT2") (pin "1") (pinfunction "1_1") (pintype "passive"))
      (node (ref "RTHERMAL") (pin "2") (pinfunction "2_2") (pintype "passive"))
      (node (ref "ST-LINK") (pin "3") (pinfunction "3_3") (pintype "passive"))
      (node (ref "USART3/FTDI") (pin "1") (pinfunction "1_1") (pintype "passive"))
      (node (ref "X4") (pin "2") (pinfunction "2_2") (pintype "passive"))
      (node (ref "XTAL2") (pin "GND") (pinfunction "GND_GND") (pintype "bidirectional"))
    )
    (net (code "94") (name "Net-(C37-Pad1)") (class "Default")
      (node (ref "C37") (pin "1") (pinfunction "1_1") (pintype "passive"))
      (node (ref "TPS63031") (pin "6") (pinfunction "6_6") (pintype "passive"))
      (node (ref "TPS63031") (pin "7") (pinfunction "7_7") (pintype "passive"))
      (node (ref "TPS63031") (pin "8") (pinfunction "8_8") (pintype "passive"))
    )
    (net (code "95") (name "Net-(D1-C)") (class "Default")
      (node (ref "D1") (pin "3") (pinfunction "C_3") (pintype "passive"))
      (node (ref "R3") (pin "2") (pinfunction "2_2") (pintype "passive"))
    )
    (net (code "96") (name "Net-(D6-PadC)") (class "Default")
      (node (ref "D6") (pin "C") (pinfunction "C_C") (pintype "passive"))
      (node (ref "IC8") (pin "1") (pinfunction "OUT_1") (pintype "output"))
      (node (ref "IC8") (pin "20") (pinfunction "OUT_20") (pintype "input"))
      (node (ref "L3") (pin "1") (pinfunction "1_1") (pintype "passive"))
    )
    (net (code "97") (name "Net-(IC8B-BAT)") (class "Default")
      (node (ref "C33") (pin "1") (pinfunction "1_1") (pintype "passive"))
      (node (ref "C35") (pin "+") (pinfunction "+_+") (pintype "passive"))
      (node (ref "C36") (pin "1") (pinfunction "1_1") (pintype "passive"))
      (node (ref "IC8") (pin "14") (pinfunction "BAT_14") (pintype "input"))
      (node (ref "L5") (pin "2") (pinfunction "2_2") (pintype "passive"))
      (node (ref "R19") (pin "1") (pinfunction "1_1") (pintype "passive"))
      (node (ref "R20") (pin "2") (pinfunction "2_2") (pintype "passive"))
      (node (ref "RSNS") (pin "2") (pinfunction "2_2") (pintype "passive"))
      (node (ref "TPS61028") (pin "7") (pinfunction "7_7") (pintype "passive"))
      (node (ref "TPS63031") (pin "5") (pinfunction "5_5") (pintype "passive"))
      (node (ref "X4") (pin "1") (pinfunction "1_1") (pintype "passive"))
    )
    (net (code "98") (name "Net-(IC8B-CELLS)") (class "Default")
      (node (ref "IC8") (pin "13") (pinfunction "CELLS_13") (pintype "input"))
      (node (ref "R10") (pin "1") (pinfunction "1_1") (pintype "passive"))
    )
    (net (code "99") (name "Net-(IC8B-IN1)") (class "Default")
      (node (ref "C26") (pin "1") (pinfunction "1_1") (pintype "passive"))
      (node (ref "CIN") (pin "1") (pinfunction "1_1") (pintype "passive"))
      (node (ref "IC8") (pin "3") (pinfunction "IN1_3") (pintype "input"))
      (node (ref "IC8") (pin "4") (pinfunction "IN2_4") (pintype "input"))
      (node (ref "IC8") (pin "6") (pinfunction "VCC_6") (pintype "input"))
      (node (ref "JP1") (pin "2") (pinfunction "2_2") (pintype "passive"))
      (node (ref "R10") (pin "2") (pinfunction "2_2") (pintype "passive"))
      (node (ref "R11") (pin "2") (pinfunction "2_2") (pintype "passive"))
      (node (ref "R12") (pin "2") (pinfunction "2_2") (pintype "passive"))
      (node (ref "R13") (pin "2") (pinfunction "2_2") (pintype "passive"))
    )
    (net (code "100") (name "Net-(IC8B-ISET1)") (class "Default")
      (node (ref "IC8") (pin "8") (pinfunction "ISET1_8") (pintype "bidirectional"))
      (node (ref "RI1") (pin "1") (pinfunction "1_1") (pintype "passive"))
    )
    (net (code "101") (name "Net-(IC8B-ISET2)") (class "Default")
      (node (ref "IC8") (pin "9") (pinfunction "ISET2_9") (pintype "bidirectional"))
      (node (ref "RI2") (pin "1") (pinfunction "1_1") (pintype "passive"))
    )
    (net (code "102") (name "Net-(IC8B-SNS)") (class "Default")
      (node (ref "CC") (pin "1") (pinfunction "1_1") (pintype "passive"))
      (node (ref "COUT") (pin "1") (pinfunction "1_1") (pintype "passive"))
      (node (ref "IC8") (pin "15") (pinfunction "SNS_15") (pintype "input"))
      (node (ref "L3") (pin "2") (pinfunction "2_2") (pintype "passive"))
      (node (ref "RSNS") (pin "1") (pinfunction "1_1") (pintype "passive"))
    )
    (net (code "103") (name "Net-(IC8B-STAT1)") (class "Default")
      (node (ref "IC8") (pin "2") (pinfunction "STAT1_2") (pintype "output"))
      (node (ref "LED1") (pin "K") (pinfunction "C_K") (pintype "passive"))
    )
    (net (code "104") (name "Net-(IC8B-STAT2)") (class "Default")
      (node (ref "IC8") (pin "19") (pinfunction "STAT2_19") (pintype "output"))
      (node (ref "LED2") (pin "K") (pinfunction "C_K") (pintype "passive"))
    )
    (net (code "105") (name "Net-(IC8B-TS)") (class "Default")
      (node (ref "IC8") (pin "12") (pinfunction "TS_12") (pintype "input"))
      (node (ref "RT1") (pin "1") (pinfunction "1_1") (pintype "passive"))
      (node (ref "RT2") (pin "2") (pinfunction "2_2") (pintype "passive"))
      (node (ref "RTHERMAL") (pin "1") (pinfunction "1_1") (pintype "passive"))
    )
    (net (code "106") (name "Net-(IC8B-TTC)") (class "Default")
      (node (ref "CTTC") (pin "1") (pinfunction "1_1") (pintype "passive"))
      (node (ref "IC8") (pin "7") (pinfunction "TTC_7") (pintype "passive"))
    )
    (net (code "107") (name "Net-(IC8B-VTSB)") (class "Default")
      (node (ref "CC1") (pin "1") (pinfunction "1_1") (pintype "passive"))
      (node (ref "IC8") (pin "11") (pinfunction "VTSB_11") (pintype "output"))
      (node (ref "RT1") (pin "2") (pinfunction "2_2") (pintype "passive"))
    )
    (net (code "108") (name "Net-(IC8B-~{PG})") (class "Default")
      (node (ref "IC8") (pin "5") (pinfunction "~{PG}_5") (pintype "output"))
      (node (ref "LED3") (pin "K") (pinfunction "C_K") (pintype "passive"))
    )
    (net (code "109") (name "Net-(L5-Pad1)") (class "Default")
      (node (ref "L5") (pin "1") (pinfunction "1_1") (pintype "passive"))
      (node (ref "TPS61028") (pin "9") (pinfunction "9_9") (pintype "passive"))
    )
    (net (code "110") (name "Net-(L6-Pad1)") (class "Default")
      (node (ref "L6") (pin "1") (pinfunction "1_1") (pintype "passive"))
      (node (ref "TPS63031") (pin "4") (pinfunction "4_4") (pintype "passive"))
    )
    (net (code "111") (name "Net-(L6-Pad2)") (class "Default")
      (node (ref "L6") (pin "2") (pinfunction "2_2") (pintype "passive"))
      (node (ref "TPS63031") (pin "2") (pinfunction "2_2") (pintype "passive"))
    )
    (net (code "112") (name "Net-(LED1-PadA)") (class "Default")
      (node (ref "LED1") (pin "A") (pinfunction "A_A") (pintype "passive"))
      (node (ref "R11") (pin "1") (pinfunction "1_1") (pintype "passive"))
    )
    (net (code "113") (name "Net-(LED2-PadA)") (class "Default")
      (node (ref "LED2") (pin "A") (pinfunction "A_A") (pintype "passive"))
      (node (ref "R12") (pin "1") (pinfunction "1_1") (pintype "passive"))
    )
    (net (code "114") (name "Net-(LED3-PadA)") (class "Default")
      (node (ref "LED3") (pin "A") (pinfunction "A_A") (pintype "passive"))
      (node (ref "R13") (pin "1") (pinfunction "1_1") (pintype "passive"))
    )
    (net (code "115") (name "Net-(LED7-PadC)") (class "Default")
      (node (ref "LED7") (pin "C") (pinfunction "C_C") (pintype "passive"))
      (node (ref "R4") (pin "2") (pinfunction "2_2") (pintype "passive"))
    )
    (net (code "116") (name "Net-(Q1-S)") (class "Default")
      (node (ref "Q1") (pin "2") (pinfunction "S_2") (pintype "passive"))
      (node (ref "Q2") (pin "2") (pinfunction "S_2") (pintype "passive"))
    )
    (net (code "117") (name "Net-(R18-Pad1)") (class "Default")
      (node (ref "R18") (pin "1") (pinfunction "1_1") (pintype "passive"))
      (node (ref "TPS61028") (pin "4") (pinfunction "4_4") (pintype "passive"))
    )
    (net (code "118") (name "Net-(R19-Pad2)") (class "Default")
      (node (ref "R19") (pin "2") (pinfunction "2_2") (pintype "passive"))
      (node (ref "TPS61028") (pin "1") (pinfunction "1_1") (pintype "passive"))
      (node (ref "TPS61028") (pin "6") (pinfunction "6_6") (pintype "passive"))
    )
    (net (code "119") (name "VCC") (class "Default")
      (node (ref "BOOT") (pin "P$2") (pinfunction "2_P$2") (pintype "passive"))
      (node (ref "C10") (pin "1") (pinfunction "1_1") (pintype "passive"))
      (node (ref "C11") (pin "1") (pinfunction "1_1") (pintype "passive"))
      (node (ref "C12") (pin "1") (pinfunction "1_1") (pintype "passive"))
      (node (ref "C6") (pin "1") (pinfunction "1_1") (pintype "passive"))
      (node (ref "C7") (pin "1") (pinfunction "1_1") (pintype "passive"))
      (node (ref "C8") (pin "1") (pinfunction "1_1") (pintype "passive"))
      (node (ref "C9") (pin "1") (pinfunction "1_1") (pintype "passive"))
      (node (ref "D1") (pin "1") (pinfunction "A_1") (pintype "passive"))
      (node (ref "FET1") (pin "2") (pinfunction "S_2") (pintype "passive"))
      (node (ref "IC1") (pin "100") (pinfunction "VDD_3_100") (pintype "power_in"))
      (node (ref "IC1") (pin "11") (pinfunction "VDD_11") (pintype "power_in"))
      (node (ref "IC1") (pin "27") (pinfunction "VDD_27") (pintype "power_in"))
      (node (ref "IC1") (pin "50") (pinfunction "VDD_2_50") (pintype "power_in"))
      (node (ref "IC1") (pin "75") (pinfunction "VDD_2_75") (pintype "power_in"))
      (node (ref "L2") (pin "1") (pinfunction "1_1") (pintype "passive"))
      (node (ref "R9") (pin "2") (pinfunction "2_2") (pintype "passive"))
      (node (ref "ST-LINK") (pin "1") (pinfunction "1_1") (pintype "passive"))
    )
    (net (code "120") (name "unconnected-(BOOTLOAD-Pad2)") (class "Default")
      (node (ref "BOOTLOAD") (pin "2") (pinfunction "2_2") (pintype "passive"))
    )
    (net (code "121") (name "unconnected-(BOOTLOAD-Pad6)") (class "Default")
      (node (ref "BOOTLOAD") (pin "6") (pinfunction "6_6") (pintype "passive"))
    )
    (net (code "122") (name "unconnected-(JP1-Pad1)") (class "Default")
      (node (ref "JP1") (pin "1") (pinfunction "1_1") (pintype "passive"))
    )
    (net (code "123") (name "unconnected-(TPS61028-Pad3)") (class "Default")
      (node (ref "TPS61028") (pin "3") (pinfunction "3_3") (pintype "passive"))
    )
    (net (code "124") (name "unconnected-(USART3/FTDI-Pad2)") (class "Default")
      (node (ref "USART3/FTDI") (pin "2") (pinfunction "2_2") (pintype "passive"))
    )
    (net (code "125") (name "unconnected-(USART3/FTDI-Pad6)") (class "Default")
      (node (ref "USART3/FTDI") (pin "6") (pinfunction "6_6") (pintype "passive"))
    )
  )
)
